# Frankie_DIYRevB.net
KiCad netlist of a schematic drawn in EAGLE
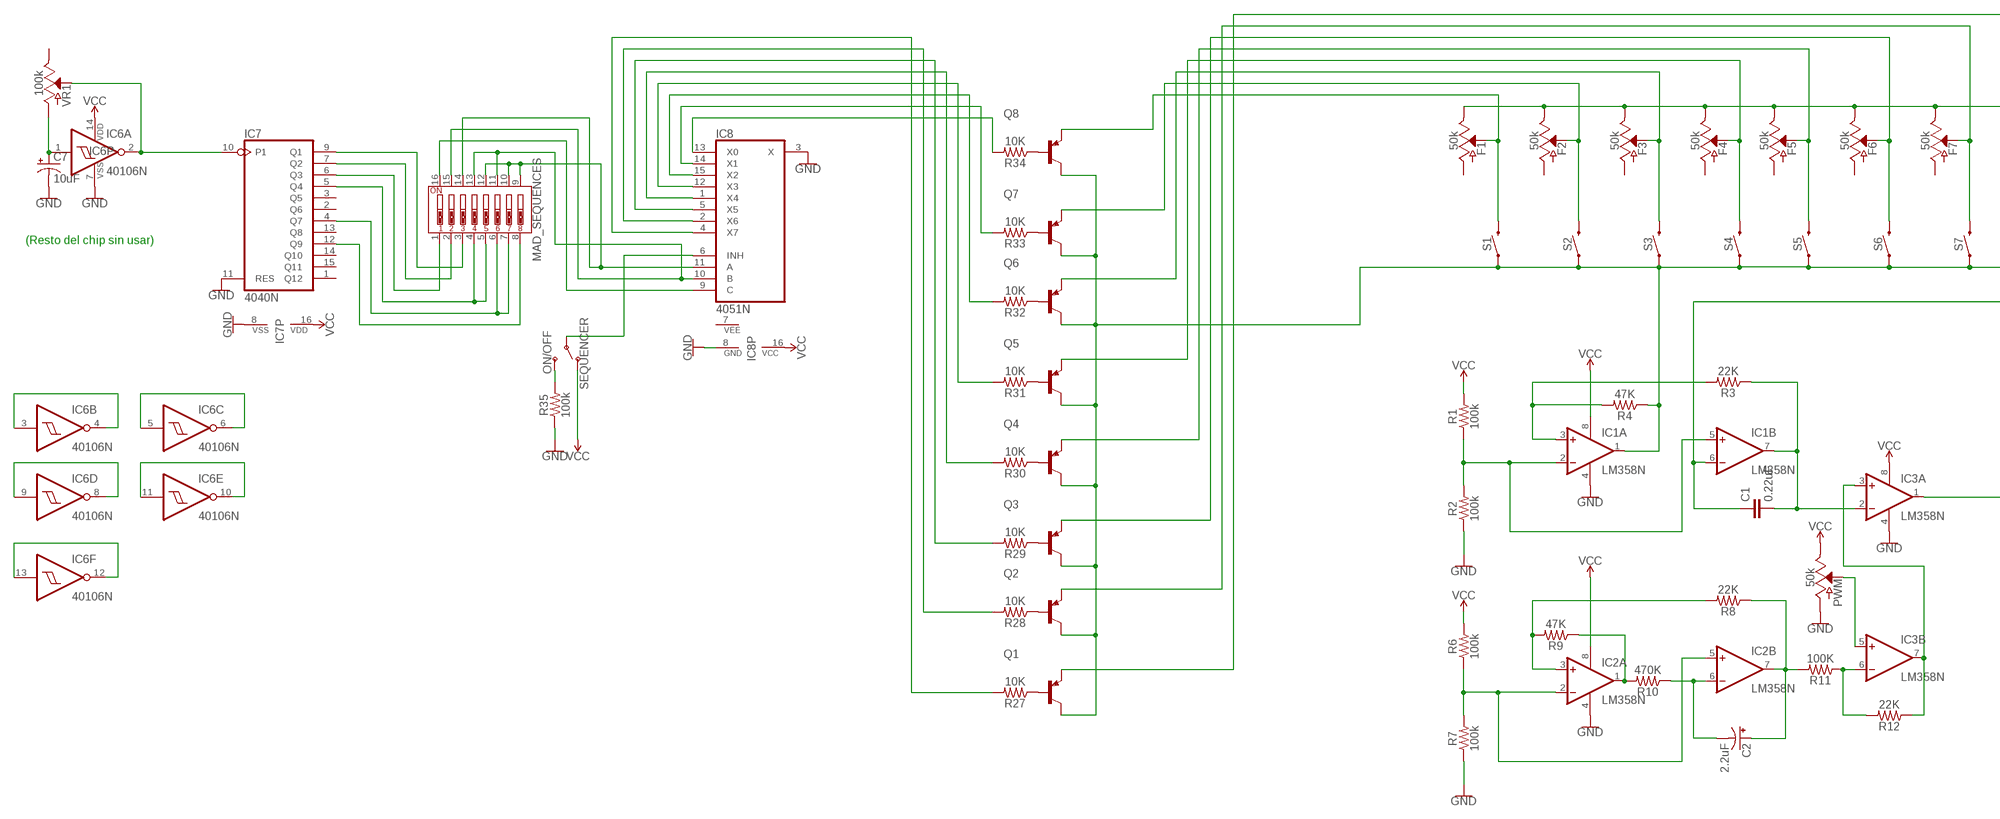
[diagram p0: schematic, sheet 1, part 1 of 2]
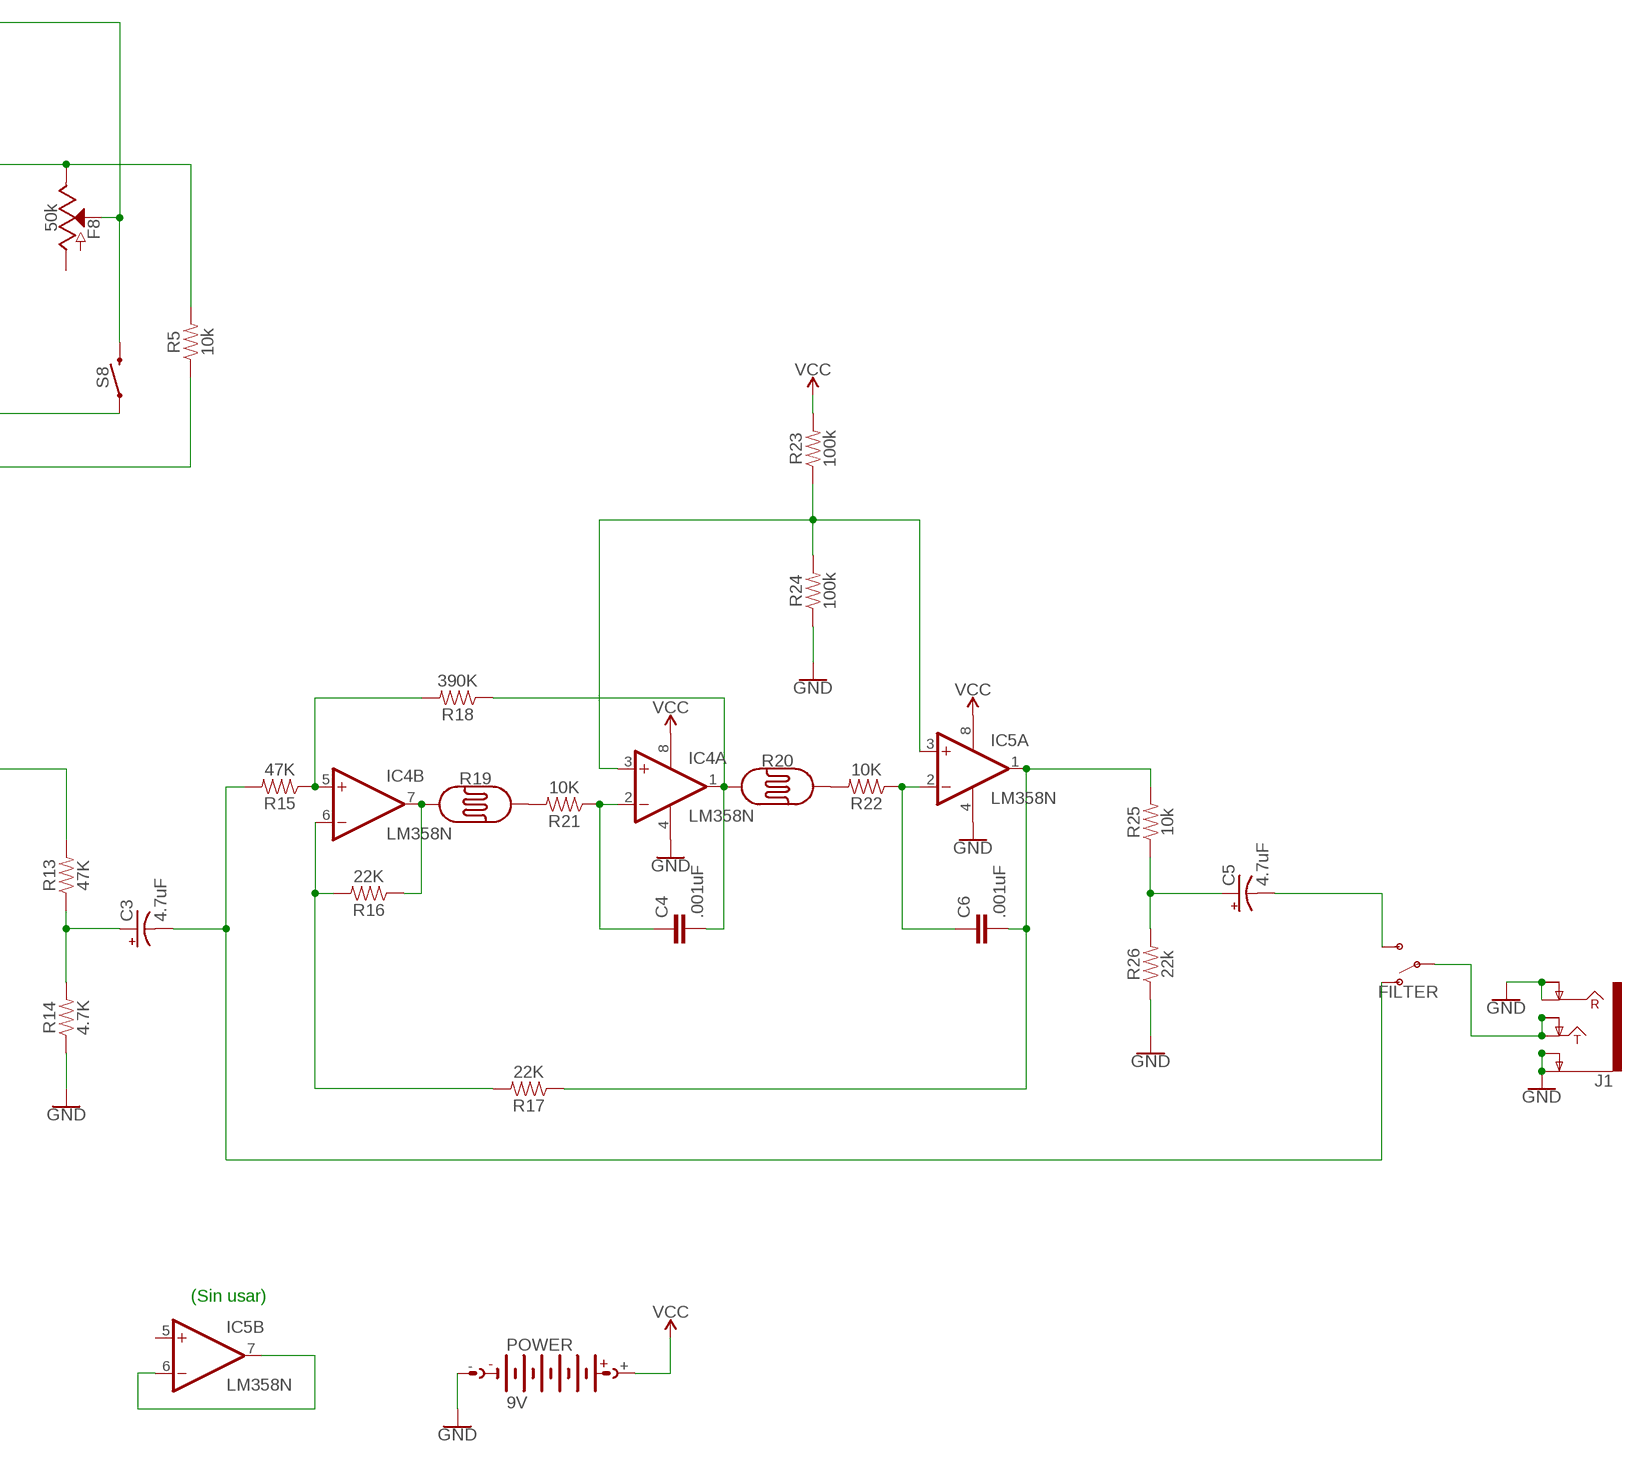
[diagram p1: schematic, sheet 1, part 2 of 2]

(export (version "E")
  (design (tool "Eeschema 10.0.6"))
  (components
    (comp (ref "C1")
      (value "0.22uF")
      (footprint "eagle-import:C5B2.5")
      (libsource (lib "eagle-import") (part "C5/2.5"))
    )
    (comp (ref "C2")
      (value "2.2uF")
      (footprint "eagle-import:CPOL-RADIAL-2.5MM-5MM-KIT")
      (libsource (lib "eagle-import") (part "10UF-POLAR-RADIAL-2.5MM-KIT-25V-20%"))
    )
    (comp (ref "C3")
      (value "4.7uF")
      (footprint "eagle-import:CPOL-RADIAL-2.5MM-5MM-KIT")
      (libsource (lib "eagle-import") (part "10UF-POLAR-RADIAL-2.5MM-KIT-25V-20%"))
    )
    (comp (ref "C4")
      (value ".001uF")
      (footprint "eagle-import:C5B2.5")
      (libsource (lib "eagle-import") (part "C5/2.5"))
    )
    (comp (ref "C5")
      (value "4.7uF")
      (footprint "eagle-import:CPOL-RADIAL-2.5MM-5MM-KIT")
      (libsource (lib "eagle-import") (part "10UF-POLAR-RADIAL-2.5MM-KIT-25V-20%"))
    )
    (comp (ref "C6")
      (value ".001uF")
      (footprint "eagle-import:C5B2.5")
      (libsource (lib "eagle-import") (part "C5/2.5"))
    )
    (comp (ref "C7")
      (value "10uF")
      (footprint "eagle-import:CPOL-RADIAL-2.5MM-5MM-KIT")
      (libsource (lib "eagle-import") (part "10UF-POLAR-RADIAL-2.5MM-KIT-25V-20%"))
    )
    (comp (ref "F1")
      (value "50k")
      (footprint "eagle-import:POT-PTH-ALPS-KIT")
      (libsource (lib "eagle-import") (part "POTENTIOMETER-PTH-9MM-1/20W-20%-KIT"))
    )
    (comp (ref "F2")
      (value "50k")
      (footprint "eagle-import:POT-PTH-ALPS-KIT")
      (libsource (lib "eagle-import") (part "POTENTIOMETER-PTH-9MM-1/20W-20%-KIT"))
    )
    (comp (ref "F3")
      (value "50k")
      (footprint "eagle-import:POT-PTH-ALPS-KIT")
      (libsource (lib "eagle-import") (part "POTENTIOMETER-PTH-9MM-1/20W-20%-KIT"))
    )
    (comp (ref "F4")
      (value "50k")
      (footprint "eagle-import:POT-PTH-ALPS-KIT")
      (libsource (lib "eagle-import") (part "POTENTIOMETER-PTH-9MM-1/20W-20%-KIT"))
    )
    (comp (ref "F5")
      (value "50k")
      (footprint "eagle-import:POT-PTH-ALPS-KIT")
      (libsource (lib "eagle-import") (part "POTENTIOMETER-PTH-9MM-1/20W-20%-KIT"))
    )
    (comp (ref "F6")
      (value "50k")
      (footprint "eagle-import:POT-PTH-ALPS-KIT")
      (libsource (lib "eagle-import") (part "POTENTIOMETER-PTH-9MM-1/20W-20%-KIT"))
    )
    (comp (ref "F7")
      (value "50k")
      (footprint "eagle-import:POT-PTH-ALPS-KIT")
      (libsource (lib "eagle-import") (part "POTENTIOMETER-PTH-9MM-1/20W-20%-KIT"))
    )
    (comp (ref "F8")
      (value "50k")
      (footprint "eagle-import:POT-PTH-ALPS-KIT")
      (libsource (lib "eagle-import") (part "POTENTIOMETER-PTH-9MM-1/20W-20%-KIT"))
    )
    (comp (ref "FILTER")
      (value "SWITCH-SPDT-PTH-11.6X4.0MM-KIT")
      (footprint "eagle-import:SWITCH_SPDT_PTH_11.6X4.0MM_KIT")
      (libsource (lib "eagle-import") (part "SWITCH-SPDT-PTH-11.6X4.0MM-KIT"))
    )
    (comp (ref "IC1")
      (value "LM358N")
      (footprint "eagle-import:DIL08")
      (libsource (lib "eagle-import") (part "LM358N"))
    )
    (comp (ref "IC2")
      (value "LM358N")
      (footprint "eagle-import:DIL08")
      (libsource (lib "eagle-import") (part "LM358N"))
    )
    (comp (ref "IC3")
      (value "LM358N")
      (footprint "eagle-import:DIL08")
      (libsource (lib "eagle-import") (part "LM358N"))
    )
    (comp (ref "IC4")
      (value "LM358N")
      (footprint "eagle-import:DIL08")
      (libsource (lib "eagle-import") (part "LM358N"))
    )
    (comp (ref "IC5")
      (value "LM358N")
      (footprint "eagle-import:DIL08")
      (libsource (lib "eagle-import") (part "LM358N"))
    )
    (comp (ref "IC6")
      (value "40106N")
      (footprint "eagle-import:DIL14")
      (libsource (lib "eagle-import") (part "40106N"))
    )
    (comp (ref "IC7")
      (value "4040N")
      (footprint "eagle-import:DIL16")
      (libsource (lib "eagle-import") (part "4040N"))
    )
    (comp (ref "IC8")
      (value "4051N")
      (footprint "eagle-import:DIL16")
      (libsource (lib "eagle-import") (part "4051N"))
    )
    (comp (ref "J1")
      (value "AUDIO_JACK_TRS_0.25\"_PTH_RA")
      (footprint "eagle-import:AUDIO_JACK_0.25__TRS_PTH_RA")
      (libsource (lib "eagle-import") (part "AUDIO_JACK_TRS_0.25{dblquote}_PTH_RA"))
    )
    (comp (ref "MAD_SEQUENCES")
      (value "DIP-08-PTH")
      (footprint "eagle-import:DIPSWITCH-08")
      (libsource (lib "eagle-import") (part "DIP-08-PTH"))
    )
    (comp (ref "POWER")
      (value "9V")
      (footprint "eagle-import:AB9V")
      (libsource (lib "eagle-import") (part "AB9V"))
    )
    (comp (ref "PWM")
      (value "50k")
      (footprint "eagle-import:POT-PTH-ALPS-KIT")
      (libsource (lib "eagle-import") (part "POTENTIOMETER-PTH-9MM-1/20W-20%-KIT"))
    )
    (comp (ref "Q1")
      (value "2N3906")
      (footprint "eagle-import:TO92")
      (libsource (lib "eagle-import") (part "2N3906"))
    )
    (comp (ref "Q2")
      (value "2N3906")
      (footprint "eagle-import:TO92")
      (libsource (lib "eagle-import") (part "2N3906"))
    )
    (comp (ref "Q3")
      (value "2N3906")
      (footprint "eagle-import:TO92")
      (libsource (lib "eagle-import") (part "2N3906"))
    )
    (comp (ref "Q4")
      (value "2N3906")
      (footprint "eagle-import:TO92")
      (libsource (lib "eagle-import") (part "2N3906"))
    )
    (comp (ref "Q5")
      (value "2N3906")
      (footprint "eagle-import:TO92")
      (libsource (lib "eagle-import") (part "2N3906"))
    )
    (comp (ref "Q6")
      (value "2N3906")
      (footprint "eagle-import:TO92")
      (libsource (lib "eagle-import") (part "2N3906"))
    )
    (comp (ref "Q7")
      (value "2N3906")
      (footprint "eagle-import:TO92")
      (libsource (lib "eagle-import") (part "2N3906"))
    )
    (comp (ref "Q8")
      (value "2N3906")
      (footprint "eagle-import:TO92")
      (libsource (lib "eagle-import") (part "2N3906"))
    )
    (comp (ref "R1")
      (value "100k")
      (footprint "eagle-import:AXIAL-0.3")
      (libsource (lib "eagle-import") (part "100KOHM-HORIZ-1/4W-5%"))
    )
    (comp (ref "R2")
      (value "100k")
      (footprint "eagle-import:AXIAL-0.3")
      (libsource (lib "eagle-import") (part "100KOHM-HORIZ-1/4W-5%"))
    )
    (comp (ref "R3")
      (value "22K")
      (footprint "eagle-import:AXIAL-0.3")
      (libsource (lib "eagle-import") (part "100KOHM-HORIZ-1/4W-5%"))
    )
    (comp (ref "R4")
      (value "47K")
      (footprint "eagle-import:AXIAL-0.3")
      (libsource (lib "eagle-import") (part "100KOHM-HORIZ-1/4W-5%"))
    )
    (comp (ref "R5")
      (value "10k")
      (footprint "eagle-import:AXIAL-0.3")
      (libsource (lib "eagle-import") (part "100KOHM-HORIZ-1/4W-5%"))
    )
    (comp (ref "R6")
      (value "100k")
      (footprint "eagle-import:AXIAL-0.3")
      (libsource (lib "eagle-import") (part "100KOHM-HORIZ-1/4W-5%"))
    )
    (comp (ref "R7")
      (value "100k")
      (footprint "eagle-import:AXIAL-0.3")
      (libsource (lib "eagle-import") (part "100KOHM-HORIZ-1/4W-5%"))
    )
    (comp (ref "R8")
      (value "22K")
      (footprint "eagle-import:AXIAL-0.3")
      (libsource (lib "eagle-import") (part "100KOHM-HORIZ-1/4W-5%"))
    )
    (comp (ref "R9")
      (value "47K")
      (footprint "eagle-import:AXIAL-0.3")
      (libsource (lib "eagle-import") (part "100KOHM-HORIZ-1/4W-5%"))
    )
    (comp (ref "R10")
      (value "470K")
      (footprint "eagle-import:AXIAL-0.3")
      (libsource (lib "eagle-import") (part "100KOHM-HORIZ-1/4W-5%"))
    )
    (comp (ref "R11")
      (value "100K")
      (footprint "eagle-import:AXIAL-0.3")
      (libsource (lib "eagle-import") (part "100KOHM-HORIZ-1/4W-5%"))
    )
    (comp (ref "R12")
      (value "22K")
      (footprint "eagle-import:AXIAL-0.3")
      (libsource (lib "eagle-import") (part "100KOHM-HORIZ-1/4W-5%"))
    )
    (comp (ref "R13")
      (value "47K")
      (footprint "eagle-import:AXIAL-0.3")
      (libsource (lib "eagle-import") (part "100KOHM-HORIZ-1/4W-5%"))
    )
    (comp (ref "R14")
      (value "4.7K")
      (footprint "eagle-import:AXIAL-0.3")
      (libsource (lib "eagle-import") (part "100KOHM-HORIZ-1/4W-5%"))
    )
    (comp (ref "R15")
      (value "47K")
      (footprint "eagle-import:AXIAL-0.3")
      (libsource (lib "eagle-import") (part "100KOHM-HORIZ-1/4W-5%"))
    )
    (comp (ref "R16")
      (value "22K")
      (footprint "eagle-import:AXIAL-0.3")
      (libsource (lib "eagle-import") (part "100KOHM-HORIZ-1/4W-5%"))
    )
    (comp (ref "R17")
      (value "22K")
      (footprint "eagle-import:AXIAL-0.3")
      (libsource (lib "eagle-import") (part "100KOHM-HORIZ-1/4W-5%"))
    )
    (comp (ref "R18")
      (value "390K")
      (footprint "eagle-import:AXIAL-0.3")
      (libsource (lib "eagle-import") (part "100KOHM-HORIZ-1/4W-5%"))
    )
    (comp (ref "R19")
      (value "PHOTOCELLPTH-KIT")
      (footprint "eagle-import:PHOTOCELL-KIT")
      (libsource (lib "eagle-import") (part "PHOTOCELLPTH-KIT"))
    )
    (comp (ref "R20")
      (value "PHOTOCELLPTH-KIT")
      (footprint "eagle-import:PHOTOCELL-KIT")
      (libsource (lib "eagle-import") (part "PHOTOCELLPTH-KIT"))
    )
    (comp (ref "R21")
      (value "10K")
      (footprint "eagle-import:AXIAL-0.3")
      (libsource (lib "eagle-import") (part "100KOHM-HORIZ-1/4W-5%"))
    )
    (comp (ref "R22")
      (value "10K")
      (footprint "eagle-import:AXIAL-0.3")
      (libsource (lib "eagle-import") (part "100KOHM-HORIZ-1/4W-5%"))
    )
    (comp (ref "R23")
      (value "100k")
      (footprint "eagle-import:AXIAL-0.3")
      (libsource (lib "eagle-import") (part "100KOHM-HORIZ-1/4W-5%"))
    )
    (comp (ref "R24")
      (value "100k")
      (footprint "eagle-import:AXIAL-0.3")
      (libsource (lib "eagle-import") (part "100KOHM-HORIZ-1/4W-5%"))
    )
    (comp (ref "R25")
      (value "10k")
      (footprint "eagle-import:AXIAL-0.3")
      (libsource (lib "eagle-import") (part "100KOHM-HORIZ-1/4W-5%"))
    )
    (comp (ref "R26")
      (value "22k")
      (footprint "eagle-import:AXIAL-0.3")
      (libsource (lib "eagle-import") (part "100KOHM-HORIZ-1/4W-5%"))
    )
    (comp (ref "R27")
      (value "10K")
      (footprint "eagle-import:AXIAL-0.3")
      (libsource (lib "eagle-import") (part "100KOHM-HORIZ-1/4W-5%"))
    )
    (comp (ref "R28")
      (value "10K")
      (footprint "eagle-import:AXIAL-0.3")
      (libsource (lib "eagle-import") (part "100KOHM-HORIZ-1/4W-5%"))
    )
    (comp (ref "R29")
      (value "10K")
      (footprint "eagle-import:AXIAL-0.3")
      (libsource (lib "eagle-import") (part "100KOHM-HORIZ-1/4W-5%"))
    )
    (comp (ref "R30")
      (value "10K")
      (footprint "eagle-import:AXIAL-0.3")
      (libsource (lib "eagle-import") (part "100KOHM-HORIZ-1/4W-5%"))
    )
    (comp (ref "R31")
      (value "10K")
      (footprint "eagle-import:AXIAL-0.3")
      (libsource (lib "eagle-import") (part "100KOHM-HORIZ-1/4W-5%"))
    )
    (comp (ref "R32")
      (value "10K")
      (footprint "eagle-import:AXIAL-0.3")
      (libsource (lib "eagle-import") (part "100KOHM-HORIZ-1/4W-5%"))
    )
    (comp (ref "R33")
      (value "10K")
      (footprint "eagle-import:AXIAL-0.3")
      (libsource (lib "eagle-import") (part "100KOHM-HORIZ-1/4W-5%"))
    )
    (comp (ref "R34")
      (value "10K")
      (footprint "eagle-import:AXIAL-0.3")
      (libsource (lib "eagle-import") (part "100KOHM-HORIZ-1/4W-5%"))
    )
    (comp (ref "R35")
      (value "100k")
      (footprint "eagle-import:AXIAL-0.3")
      (libsource (lib "eagle-import") (part "100KOHM-HORIZ-1/4W-5%"))
    )
    (comp (ref "S1")
      (value "MOMENTARY-SWITCH-SPST-PTH-12MM")
      (footprint "eagle-import:TACTILE_SWITCH_PTH_12MM")
      (libsource (lib "eagle-import") (part "MOMENTARY-SWITCH-SPST-PTH-12MM"))
    )
    (comp (ref "S2")
      (value "MOMENTARY-SWITCH-SPST-PTH-12MM")
      (footprint "eagle-import:TACTILE_SWITCH_PTH_12MM")
      (libsource (lib "eagle-import") (part "MOMENTARY-SWITCH-SPST-PTH-12MM"))
    )
    (comp (ref "S3")
      (value "MOMENTARY-SWITCH-SPST-PTH-12MM")
      (footprint "eagle-import:TACTILE_SWITCH_PTH_12MM")
      (libsource (lib "eagle-import") (part "MOMENTARY-SWITCH-SPST-PTH-12MM"))
    )
    (comp (ref "S4")
      (value "MOMENTARY-SWITCH-SPST-PTH-12MM")
      (footprint "eagle-import:TACTILE_SWITCH_PTH_12MM")
      (libsource (lib "eagle-import") (part "MOMENTARY-SWITCH-SPST-PTH-12MM"))
    )
    (comp (ref "S5")
      (value "MOMENTARY-SWITCH-SPST-PTH-12MM")
      (footprint "eagle-import:TACTILE_SWITCH_PTH_12MM")
      (libsource (lib "eagle-import") (part "MOMENTARY-SWITCH-SPST-PTH-12MM"))
    )
    (comp (ref "S6")
      (value "MOMENTARY-SWITCH-SPST-PTH-12MM")
      (footprint "eagle-import:TACTILE_SWITCH_PTH_12MM")
      (libsource (lib "eagle-import") (part "MOMENTARY-SWITCH-SPST-PTH-12MM"))
    )
    (comp (ref "S7")
      (value "MOMENTARY-SWITCH-SPST-PTH-12MM")
      (footprint "eagle-import:TACTILE_SWITCH_PTH_12MM")
      (libsource (lib "eagle-import") (part "MOMENTARY-SWITCH-SPST-PTH-12MM"))
    )
    (comp (ref "S8")
      (value "MOMENTARY-SWITCH-SPST-PTH-12MM")
      (footprint "eagle-import:TACTILE_SWITCH_PTH_12MM")
      (libsource (lib "eagle-import") (part "MOMENTARY-SWITCH-SPST-PTH-12MM"))
    )
    (comp (ref "SEQUENCER")
      (value "ON/OFF")
      (footprint "eagle-import:SWITCH_SPDT_PTH_11.6X4.0MM_KIT")
      (libsource (lib "eagle-import") (part "SWITCH-SPDT-PTH-11.6X4.0MM-KIT"))
    )
    (comp (ref "VR1")
      (value "100k")
      (footprint "eagle-import:POT-PTH-ALPS-KIT")
      (libsource (lib "eagle-import") (part "POTENTIOMETER-PTH-9MM-1/20W-20%-KIT"))
    )
  )
  (nets
    (net (code "1") (name "/VEE") (class "Default")
      (node (ref "IC8") (pin "7") (pinfunction "VEE_7") (pintype "power_in"))
    )
    (net (code "2") (name "GND") (class "Default")
      (node (ref "C7") (pin "2") (pinfunction "-_2") (pintype "passive"))
      (node (ref "IC1") (pin "4") (pinfunction "V-_4") (pintype "power_in"))
      (node (ref "IC2") (pin "4") (pinfunction "V-_4") (pintype "power_in"))
      (node (ref "IC3") (pin "4") (pinfunction "V-_4") (pintype "power_in"))
      (node (ref "IC4") (pin "4") (pinfunction "V-_4") (pintype "power_in"))
      (node (ref "IC5") (pin "4") (pinfunction "V-_4") (pintype "power_in"))
      (node (ref "IC6") (pin "7") (pinfunction "VSS_7") (pintype "power_in"))
      (node (ref "IC7") (pin "11") (pinfunction "RES_11") (pintype "input"))
      (node (ref "IC7") (pin "8") (pinfunction "VSS_8") (pintype "power_in"))
      (node (ref "IC8") (pin "3") (pinfunction "X_3") (pintype "bidirectional"))
      (node (ref "IC8") (pin "8") (pinfunction "GND_8") (pintype "power_in"))
      (node (ref "J1") (pin "RING") (pinfunction "RING_RING") (pintype "bidirectional"))
      (node (ref "J1") (pin "RING-NORM") (pinfunction "RING-NORM_RING-NORM") (pintype "bidirectional"))
      (node (ref "J1") (pin "SLEEVE") (pinfunction "EARTH_SLEEVE") (pintype "bidirectional"))
      (node (ref "J1") (pin "SLEEVE-NORM") (pinfunction "EARTH-NORM_SLEEVE-NORM") (pintype "bidirectional"))
      (node (ref "POWER") (pin "-") (pinfunction "-_-") (pintype "passive"))
      (node (ref "PWM") (pin "P$3") (pinfunction "A_P$3") (pintype "passive"))
      (node (ref "R14") (pin "P$1") (pinfunction "1_P$1") (pintype "passive"))
      (node (ref "R2") (pin "P$1") (pinfunction "1_P$1") (pintype "passive"))
      (node (ref "R24") (pin "P$1") (pinfunction "1_P$1") (pintype "passive"))
      (node (ref "R26") (pin "P$1") (pinfunction "1_P$1") (pintype "passive"))
      (node (ref "R35") (pin "P$1") (pinfunction "1_P$1") (pintype "passive"))
      (node (ref "R7") (pin "P$1") (pinfunction "1_P$1") (pintype "passive"))
    )
    (net (code "3") (name "Net-(C2-+)") (class "Default")
      (node (ref "C2") (pin "1") (pinfunction "+_1") (pintype "passive"))
      (node (ref "IC2") (pin "7") (pinfunction "OUT_7") (pintype "output"))
      (node (ref "R11") (pin "P$2") (pinfunction "2_P$2") (pintype "passive"))
      (node (ref "R8") (pin "P$1") (pinfunction "1_P$1") (pintype "passive"))
    )
    (net (code "4") (name "Net-(C2--)") (class "Default")
      (node (ref "C2") (pin "2") (pinfunction "-_2") (pintype "passive"))
      (node (ref "IC2") (pin "6") (pinfunction "-IN_6") (pintype "input"))
      (node (ref "R10") (pin "P$1") (pinfunction "1_P$1") (pintype "passive"))
    )
    (net (code "5") (name "Net-(C3-+)") (class "Default")
      (node (ref "C3") (pin "1") (pinfunction "+_1") (pintype "passive"))
      (node (ref "R13") (pin "P$1") (pinfunction "1_P$1") (pintype "passive"))
      (node (ref "R14") (pin "P$2") (pinfunction "2_P$2") (pintype "passive"))
    )
    (net (code "6") (name "Net-(C3--)") (class "Default")
      (node (ref "C3") (pin "2") (pinfunction "-_2") (pintype "passive"))
      (node (ref "FILTER") (pin "1") (pinfunction "O_1") (pintype "passive"))
      (node (ref "R15") (pin "P$2") (pinfunction "2_P$2") (pintype "passive"))
    )
    (net (code "7") (name "Net-(C5-+)") (class "Default")
      (node (ref "C5") (pin "1") (pinfunction "+_1") (pintype "passive"))
      (node (ref "R25") (pin "P$1") (pinfunction "1_P$1") (pintype "passive"))
      (node (ref "R26") (pin "P$2") (pinfunction "2_P$2") (pintype "passive"))
    )
    (net (code "8") (name "Net-(C5--)") (class "Default")
      (node (ref "C5") (pin "2") (pinfunction "-_2") (pintype "passive"))
      (node (ref "FILTER") (pin "3") (pinfunction "S_3") (pintype "passive"))
    )
    (net (code "9") (name "Net-(C7-+)") (class "Default")
      (node (ref "C7") (pin "1") (pinfunction "+_1") (pintype "passive"))
      (node (ref "IC6") (pin "1") (pinfunction "I_1") (pintype "input"))
      (node (ref "VR1") (pin "P$3") (pinfunction "A_P$3") (pintype "passive"))
    )
    (net (code "10") (name "Net-(F1-E)") (class "Default")
      (node (ref "F1") (pin "P$1") (pinfunction "E_P$1") (pintype "passive"))
      (node (ref "F2") (pin "P$1") (pinfunction "E_P$1") (pintype "passive"))
      (node (ref "F3") (pin "P$1") (pinfunction "E_P$1") (pintype "passive"))
      (node (ref "F4") (pin "P$1") (pinfunction "E_P$1") (pintype "passive"))
      (node (ref "F5") (pin "P$1") (pinfunction "E_P$1") (pintype "passive"))
      (node (ref "F6") (pin "P$1") (pinfunction "E_P$1") (pintype "passive"))
      (node (ref "F7") (pin "P$1") (pinfunction "E_P$1") (pintype "passive"))
      (node (ref "F8") (pin "P$1") (pinfunction "E_P$1") (pintype "passive"))
      (node (ref "R5") (pin "P$2") (pinfunction "2_P$2") (pintype "passive"))
    )
    (net (code "11") (name "Net-(F1-S)") (class "Default")
      (node (ref "F1") (pin "P$2") (pinfunction "S_P$2") (pintype "passive"))
      (node (ref "Q8") (pin "3") (pinfunction "E_3") (pintype "passive"))
      (node (ref "S1") (pin "3") (pinfunction "2_3") (pintype "passive"))
    )
    (net (code "12") (name "Net-(F2-S)") (class "Default")
      (node (ref "F2") (pin "P$2") (pinfunction "S_P$2") (pintype "passive"))
      (node (ref "Q7") (pin "3") (pinfunction "E_3") (pintype "passive"))
      (node (ref "S2") (pin "3") (pinfunction "2_3") (pintype "passive"))
    )
    (net (code "13") (name "Net-(F3-S)") (class "Default")
      (node (ref "F3") (pin "P$2") (pinfunction "S_P$2") (pintype "passive"))
      (node (ref "Q6") (pin "3") (pinfunction "E_3") (pintype "passive"))
      (node (ref "S3") (pin "3") (pinfunction "2_3") (pintype "passive"))
    )
    (net (code "14") (name "Net-(F4-S)") (class "Default")
      (node (ref "F4") (pin "P$2") (pinfunction "S_P$2") (pintype "passive"))
      (node (ref "Q5") (pin "3") (pinfunction "E_3") (pintype "passive"))
      (node (ref "S4") (pin "3") (pinfunction "2_3") (pintype "passive"))
    )
    (net (code "15") (name "Net-(F5-S)") (class "Default")
      (node (ref "F5") (pin "P$2") (pinfunction "S_P$2") (pintype "passive"))
      (node (ref "Q4") (pin "3") (pinfunction "E_3") (pintype "passive"))
      (node (ref "S5") (pin "3") (pinfunction "2_3") (pintype "passive"))
    )
    (net (code "16") (name "Net-(F6-S)") (class "Default")
      (node (ref "F6") (pin "P$2") (pinfunction "S_P$2") (pintype "passive"))
      (node (ref "Q3") (pin "3") (pinfunction "E_3") (pintype "passive"))
      (node (ref "S6") (pin "3") (pinfunction "2_3") (pintype "passive"))
    )
    (net (code "17") (name "Net-(F7-S)") (class "Default")
      (node (ref "F7") (pin "P$2") (pinfunction "S_P$2") (pintype "passive"))
      (node (ref "Q2") (pin "3") (pinfunction "E_3") (pintype "passive"))
      (node (ref "S7") (pin "3") (pinfunction "2_3") (pintype "passive"))
    )
    (net (code "18") (name "Net-(F8-S)") (class "Default")
      (node (ref "F8") (pin "P$2") (pinfunction "S_P$2") (pintype "passive"))
      (node (ref "Q1") (pin "3") (pinfunction "E_3") (pintype "passive"))
      (node (ref "S8") (pin "3") (pinfunction "2_3") (pintype "passive"))
    )
    (net (code "19") (name "Net-(FILTER-P)") (class "Default")
      (node (ref "FILTER") (pin "2") (pinfunction "P_2") (pintype "passive"))
      (node (ref "J1") (pin "TIP") (pinfunction "TIP_TIP") (pintype "bidirectional"))
      (node (ref "J1") (pin "TIP-NORM") (pinfunction "TIP-NORM_TIP-NORM") (pintype "bidirectional"))
    )
    (net (code "20") (name "Net-(IC1A-+IN)") (class "Default")
      (node (ref "IC1") (pin "3") (pinfunction "+IN_3") (pintype "input"))
      (node (ref "R3") (pin "P$2") (pinfunction "2_P$2") (pintype "passive"))
      (node (ref "R4") (pin "P$2") (pinfunction "2_P$2") (pintype "passive"))
    )
    (net (code "21") (name "Net-(IC1A--IN)") (class "Default")
      (node (ref "IC1") (pin "2") (pinfunction "-IN_2") (pintype "input"))
      (node (ref "IC1") (pin "5") (pinfunction "+IN_5") (pintype "input"))
      (node (ref "R1") (pin "P$1") (pinfunction "1_P$1") (pintype "passive"))
      (node (ref "R2") (pin "P$2") (pinfunction "2_P$2") (pintype "passive"))
    )
    (net (code "22") (name "Net-(IC1A-OUT)") (class "Default")
      (node (ref "IC1") (pin "1") (pinfunction "OUT_1") (pintype "output"))
      (node (ref "Q1") (pin "1") (pinfunction "C_1") (pintype "passive"))
      (node (ref "Q2") (pin "1") (pinfunction "C_1") (pintype "passive"))
      (node (ref "Q3") (pin "1") (pinfunction "C_1") (pintype "passive"))
      (node (ref "Q4") (pin "1") (pinfunction "C_1") (pintype "passive"))
      (node (ref "Q5") (pin "1") (pinfunction "C_1") (pintype "passive"))
      (node (ref "Q6") (pin "1") (pinfunction "C_1") (pintype "passive"))
      (node (ref "Q7") (pin "1") (pinfunction "C_1") (pintype "passive"))
      (node (ref "Q8") (pin "1") (pinfunction "C_1") (pintype "passive"))
      (node (ref "R4") (pin "P$1") (pinfunction "1_P$1") (pintype "passive"))
      (node (ref "S1") (pin "1") (pinfunction "1_1") (pintype "passive"))
      (node (ref "S2") (pin "1") (pinfunction "1_1") (pintype "passive"))
      (node (ref "S3") (pin "1") (pinfunction "1_1") (pintype "passive"))
      (node (ref "S4") (pin "1") (pinfunction "1_1") (pintype "passive"))
      (node (ref "S5") (pin "1") (pinfunction "1_1") (pintype "passive"))
      (node (ref "S6") (pin "1") (pinfunction "1_1") (pintype "passive"))
      (node (ref "S7") (pin "1") (pinfunction "1_1") (pintype "passive"))
      (node (ref "S8") (pin "1") (pinfunction "1_1") (pintype "passive"))
    )
    (net (code "23") (name "Net-(IC1B--IN)") (class "Default")
      (node (ref "C1") (pin "1") (pinfunction "1_1") (pintype "passive"))
      (node (ref "IC1") (pin "6") (pinfunction "-IN_6") (pintype "input"))
      (node (ref "R5") (pin "P$1") (pinfunction "1_P$1") (pintype "passive"))
    )
    (net (code "24") (name "Net-(IC1B-OUT)") (class "Default")
      (node (ref "C1") (pin "2") (pinfunction "2_2") (pintype "passive"))
      (node (ref "IC1") (pin "7") (pinfunction "OUT_7") (pintype "output"))
      (node (ref "IC3") (pin "2") (pinfunction "-IN_2") (pintype "input"))
      (node (ref "R3") (pin "P$1") (pinfunction "1_P$1") (pintype "passive"))
    )
    (net (code "25") (name "Net-(IC2A-+IN)") (class "Default")
      (node (ref "IC2") (pin "3") (pinfunction "+IN_3") (pintype "input"))
      (node (ref "R8") (pin "P$2") (pinfunction "2_P$2") (pintype "passive"))
      (node (ref "R9") (pin "P$2") (pinfunction "2_P$2") (pintype "passive"))
    )
    (net (code "26") (name "Net-(IC2A--IN)") (class "Default")
      (node (ref "IC2") (pin "2") (pinfunction "-IN_2") (pintype "input"))
      (node (ref "IC2") (pin "5") (pinfunction "+IN_5") (pintype "input"))
      (node (ref "R6") (pin "P$1") (pinfunction "1_P$1") (pintype "passive"))
      (node (ref "R7") (pin "P$2") (pinfunction "2_P$2") (pintype "passive"))
    )
    (net (code "27") (name "Net-(IC2A-OUT)") (class "Default")
      (node (ref "IC2") (pin "1") (pinfunction "OUT_1") (pintype "output"))
      (node (ref "R10") (pin "P$2") (pinfunction "2_P$2") (pintype "passive"))
      (node (ref "R9") (pin "P$1") (pinfunction "1_P$1") (pintype "passive"))
    )
    (net (code "28") (name "Net-(IC3A-+IN)") (class "Default")
      (node (ref "IC3") (pin "3") (pinfunction "+IN_3") (pintype "input"))
      (node (ref "IC3") (pin "7") (pinfunction "OUT_7") (pintype "output"))
      (node (ref "R12") (pin "P$1") (pinfunction "1_P$1") (pintype "passive"))
    )
    (net (code "29") (name "Net-(IC3A-OUT)") (class "Default")
      (node (ref "IC3") (pin "1") (pinfunction "OUT_1") (pintype "output"))
      (node (ref "R13") (pin "P$2") (pinfunction "2_P$2") (pintype "passive"))
    )
    (net (code "30") (name "Net-(IC3B-+IN)") (class "Default")
      (node (ref "IC3") (pin "5") (pinfunction "+IN_5") (pintype "input"))
      (node (ref "PWM") (pin "P$2") (pinfunction "S_P$2") (pintype "passive"))
    )
    (net (code "31") (name "Net-(IC3B--IN)") (class "Default")
      (node (ref "IC3") (pin "6") (pinfunction "-IN_6") (pintype "input"))
      (node (ref "R11") (pin "P$1") (pinfunction "1_P$1") (pintype "passive"))
      (node (ref "R12") (pin "P$2") (pinfunction "2_P$2") (pintype "passive"))
    )
    (net (code "32") (name "Net-(IC4A-+IN)") (class "Default")
      (node (ref "IC4") (pin "3") (pinfunction "+IN_3") (pintype "input"))
      (node (ref "IC5") (pin "3") (pinfunction "+IN_3") (pintype "input"))
      (node (ref "R23") (pin "P$1") (pinfunction "1_P$1") (pintype "passive"))
      (node (ref "R24") (pin "P$2") (pinfunction "2_P$2") (pintype "passive"))
    )
    (net (code "33") (name "Net-(IC4A--IN)") (class "Default")
      (node (ref "C4") (pin "1") (pinfunction "1_1") (pintype "passive"))
      (node (ref "IC4") (pin "2") (pinfunction "-IN_2") (pintype "input"))
      (node (ref "R21") (pin "P$1") (pinfunction "1_P$1") (pintype "passive"))
    )
    (net (code "34") (name "Net-(IC4A-OUT)") (class "Default")
      (node (ref "C4") (pin "2") (pinfunction "2_2") (pintype "passive"))
      (node (ref "IC4") (pin "1") (pinfunction "OUT_1") (pintype "output"))
      (node (ref "R18") (pin "P$1") (pinfunction "1_P$1") (pintype "passive"))
      (node (ref "R20") (pin "1") (pinfunction "P$1_1") (pintype "bidirectional"))
    )
    (net (code "35") (name "Net-(IC4B-+IN)") (class "Default")
      (node (ref "IC4") (pin "5") (pinfunction "+IN_5") (pintype "input"))
      (node (ref "R15") (pin "P$1") (pinfunction "1_P$1") (pintype "passive"))
      (node (ref "R18") (pin "P$2") (pinfunction "2_P$2") (pintype "passive"))
    )
    (net (code "36") (name "Net-(IC4B--IN)") (class "Default")
      (node (ref "IC4") (pin "6") (pinfunction "-IN_6") (pintype "input"))
      (node (ref "R16") (pin "P$2") (pinfunction "2_P$2") (pintype "passive"))
      (node (ref "R17") (pin "P$2") (pinfunction "2_P$2") (pintype "passive"))
    )
    (net (code "37") (name "Net-(IC4B-OUT)") (class "Default")
      (node (ref "IC4") (pin "7") (pinfunction "OUT_7") (pintype "output"))
      (node (ref "R16") (pin "P$1") (pinfunction "1_P$1") (pintype "passive"))
      (node (ref "R19") (pin "1") (pinfunction "P$1_1") (pintype "bidirectional"))
    )
    (net (code "38") (name "Net-(IC5A--IN)") (class "Default")
      (node (ref "C6") (pin "1") (pinfunction "1_1") (pintype "passive"))
      (node (ref "IC5") (pin "2") (pinfunction "-IN_2") (pintype "input"))
      (node (ref "R22") (pin "P$1") (pinfunction "1_P$1") (pintype "passive"))
    )
    (net (code "39") (name "Net-(IC5A-OUT)") (class "Default")
      (node (ref "C6") (pin "2") (pinfunction "2_2") (pintype "passive"))
      (node (ref "IC5") (pin "1") (pinfunction "OUT_1") (pintype "output"))
      (node (ref "R17") (pin "P$1") (pinfunction "1_P$1") (pintype "passive"))
      (node (ref "R25") (pin "P$2") (pinfunction "2_P$2") (pintype "passive"))
    )
    (net (code "40") (name "Net-(IC5B--IN)") (class "Default")
      (node (ref "IC5") (pin "6") (pinfunction "-IN_6") (pintype "input"))
      (node (ref "IC5") (pin "7") (pinfunction "OUT_7") (pintype "output"))
    )
    (net (code "41") (name "Net-(IC6A-O)") (class "Default")
      (node (ref "IC6") (pin "2") (pinfunction "O_2") (pintype "output"))
      (node (ref "IC7") (pin "10") (pinfunction "P1_10") (pintype "input"))
      (node (ref "VR1") (pin "P$2") (pinfunction "S_P$2") (pintype "passive"))
    )
    (net (code "42") (name "Net-(IC6B-I)") (class "Default")
      (node (ref "IC6") (pin "3") (pinfunction "I_3") (pintype "input"))
      (node (ref "IC6") (pin "4") (pinfunction "O_4") (pintype "output"))
    )
    (net (code "43") (name "Net-(IC6C-I)") (class "Default")
      (node (ref "IC6") (pin "5") (pinfunction "I_5") (pintype "input"))
      (node (ref "IC6") (pin "6") (pinfunction "O_6") (pintype "output"))
    )
    (net (code "44") (name "Net-(IC6D-I)") (class "Default")
      (node (ref "IC6") (pin "8") (pinfunction "O_8") (pintype "output"))
      (node (ref "IC6") (pin "9") (pinfunction "I_9") (pintype "input"))
    )
    (net (code "45") (name "Net-(IC6E-I)") (class "Default")
      (node (ref "IC6") (pin "10") (pinfunction "O_10") (pintype "output"))
      (node (ref "IC6") (pin "11") (pinfunction "I_11") (pintype "input"))
    )
    (net (code "46") (name "Net-(IC6F-I)") (class "Default")
      (node (ref "IC6") (pin "12") (pinfunction "O_12") (pintype "output"))
      (node (ref "IC6") (pin "13") (pinfunction "I_13") (pintype "input"))
    )
    (net (code "47") (name "Net-(IC7A-Q1)") (class "Default")
      (node (ref "IC7") (pin "9") (pinfunction "Q1_9") (pintype "output"))
      (node (ref "MAD_SEQUENCES") (pin "3") (pinfunction "3_3") (pintype "passive"))
    )
    (net (code "48") (name "Net-(IC7A-Q2)") (class "Default")
      (node (ref "IC7") (pin "7") (pinfunction "Q2_7") (pintype "output"))
      (node (ref "MAD_SEQUENCES") (pin "2") (pinfunction "2_2") (pintype "passive"))
    )
    (net (code "49") (name "Net-(IC7A-Q3)") (class "Default")
      (node (ref "IC7") (pin "6") (pinfunction "Q3_6") (pintype "output"))
      (node (ref "MAD_SEQUENCES") (pin "1") (pinfunction "1_1") (pintype "passive"))
    )
    (net (code "50") (name "Net-(IC7A-Q4)") (class "Default")
      (node (ref "IC7") (pin "5") (pinfunction "Q4_5") (pintype "output"))
      (node (ref "MAD_SEQUENCES") (pin "4") (pinfunction "4_4") (pintype "passive"))
      (node (ref "MAD_SEQUENCES") (pin "5") (pinfunction "5_5") (pintype "passive"))
    )
    (net (code "51") (name "Net-(IC7A-Q7)") (class "Default")
      (node (ref "IC7") (pin "4") (pinfunction "Q7_4") (pintype "output"))
      (node (ref "MAD_SEQUENCES") (pin "6") (pinfunction "6_6") (pintype "passive"))
      (node (ref "MAD_SEQUENCES") (pin "7") (pinfunction "7_7") (pintype "passive"))
    )
    (net (code "52") (name "Net-(IC7A-Q9)") (class "Default")
      (node (ref "IC7") (pin "12") (pinfunction "Q9_12") (pintype "output"))
      (node (ref "MAD_SEQUENCES") (pin "8") (pinfunction "8_8") (pintype "passive"))
    )
    (net (code "53") (name "Net-(IC8A-A)") (class "Default")
      (node (ref "IC8") (pin "11") (pinfunction "A_11") (pintype "input"))
      (node (ref "MAD_SEQUENCES") (pin "10") (pinfunction "10_10") (pintype "passive"))
      (node (ref "MAD_SEQUENCES") (pin "12") (pinfunction "12_12") (pintype "passive"))
      (node (ref "MAD_SEQUENCES") (pin "14") (pinfunction "14_14") (pintype "passive"))
      (node (ref "MAD_SEQUENCES") (pin "9") (pinfunction "9_9") (pintype "passive"))
    )
    (net (code "54") (name "Net-(IC8A-B)") (class "Default")
      (node (ref "IC8") (pin "10") (pinfunction "B_10") (pintype "input"))
      (node (ref "MAD_SEQUENCES") (pin "11") (pinfunction "11_11") (pintype "passive"))
      (node (ref "MAD_SEQUENCES") (pin "13") (pinfunction "13_13") (pintype "passive"))
      (node (ref "MAD_SEQUENCES") (pin "15") (pinfunction "15_15") (pintype "passive"))
    )
    (net (code "55") (name "Net-(IC8A-C)") (class "Default")
      (node (ref "IC8") (pin "9") (pinfunction "C_9") (pintype "input"))
      (node (ref "MAD_SEQUENCES") (pin "16") (pinfunction "16_16") (pintype "passive"))
    )
    (net (code "56") (name "Net-(IC8A-INH)") (class "Default")
      (node (ref "IC8") (pin "6") (pinfunction "INH_6") (pintype "input"))
      (node (ref "SEQUENCER") (pin "2") (pinfunction "P_2") (pintype "passive"))
    )
    (net (code "57") (name "Net-(IC8A-X0)") (class "Default")
      (node (ref "IC8") (pin "13") (pinfunction "X0_13") (pintype "bidirectional"))
      (node (ref "R34") (pin "P$2") (pinfunction "2_P$2") (pintype "passive"))
    )
    (net (code "58") (name "Net-(IC8A-X1)") (class "Default")
      (node (ref "IC8") (pin "14") (pinfunction "X1_14") (pintype "bidirectional"))
      (node (ref "R33") (pin "P$2") (pinfunction "2_P$2") (pintype "passive"))
    )
    (net (code "59") (name "Net-(IC8A-X2)") (class "Default")
      (node (ref "IC8") (pin "15") (pinfunction "X2_15") (pintype "bidirectional"))
      (node (ref "R32") (pin "P$2") (pinfunction "2_P$2") (pintype "passive"))
    )
    (net (code "60") (name "Net-(IC8A-X3)") (class "Default")
      (node (ref "IC8") (pin "12") (pinfunction "X3_12") (pintype "bidirectional"))
      (node (ref "R31") (pin "P$2") (pinfunction "2_P$2") (pintype "passive"))
    )
    (net (code "61") (name "Net-(IC8A-X4)") (class "Default")
      (node (ref "IC8") (pin "1") (pinfunction "X4_1") (pintype "bidirectional"))
      (node (ref "R30") (pin "P$2") (pinfunction "2_P$2") (pintype "passive"))
    )
    (net (code "62") (name "Net-(IC8A-X5)") (class "Default")
      (node (ref "IC8") (pin "5") (pinfunction "X5_5") (pintype "bidirectional"))
      (node (ref "R29") (pin "P$2") (pinfunction "2_P$2") (pintype "passive"))
    )
    (net (code "63") (name "Net-(IC8A-X6)") (class "Default")
      (node (ref "IC8") (pin "2") (pinfunction "X6_2") (pintype "bidirectional"))
      (node (ref "R28") (pin "P$2") (pinfunction "2_P$2") (pintype "passive"))
    )
    (net (code "64") (name "Net-(IC8A-X7)") (class "Default")
      (node (ref "IC8") (pin "4") (pinfunction "X7_4") (pintype "bidirectional"))
      (node (ref "R27") (pin "P$2") (pinfunction "2_P$2") (pintype "passive"))
    )
    (net (code "65") (name "Net-(Q1-B)") (class "Default")
      (node (ref "Q1") (pin "2") (pinfunction "B_2") (pintype "passive"))
      (node (ref "R27") (pin "P$1") (pinfunction "1_P$1") (pintype "passive"))
    )
    (net (code "66") (name "Net-(Q2-B)") (class "Default")
      (node (ref "Q2") (pin "2") (pinfunction "B_2") (pintype "passive"))
      (node (ref "R28") (pin "P$1") (pinfunction "1_P$1") (pintype "passive"))
    )
    (net (code "67") (name "Net-(Q3-B)") (class "Default")
      (node (ref "Q3") (pin "2") (pinfunction "B_2") (pintype "passive"))
      (node (ref "R29") (pin "P$1") (pinfunction "1_P$1") (pintype "passive"))
    )
    (net (code "68") (name "Net-(Q4-B)") (class "Default")
      (node (ref "Q4") (pin "2") (pinfunction "B_2") (pintype "passive"))
      (node (ref "R30") (pin "P$1") (pinfunction "1_P$1") (pintype "passive"))
    )
    (net (code "69") (name "Net-(Q5-B)") (class "Default")
      (node (ref "Q5") (pin "2") (pinfunction "B_2") (pintype "passive"))
      (node (ref "R31") (pin "P$1") (pinfunction "1_P$1") (pintype "passive"))
    )
    (net (code "70") (name "Net-(Q6-B)") (class "Default")
      (node (ref "Q6") (pin "2") (pinfunction "B_2") (pintype "passive"))
      (node (ref "R32") (pin "P$1") (pinfunction "1_P$1") (pintype "passive"))
    )
    (net (code "71") (name "Net-(Q7-B)") (class "Default")
      (node (ref "Q7") (pin "2") (pinfunction "B_2") (pintype "passive"))
      (node (ref "R33") (pin "P$1") (pinfunction "1_P$1") (pintype "passive"))
    )
    (net (code "72") (name "Net-(Q8-B)") (class "Default")
      (node (ref "Q8") (pin "2") (pinfunction "B_2") (pintype "passive"))
      (node (ref "R34") (pin "P$1") (pinfunction "1_P$1") (pintype "passive"))
    )
    (net (code "73") (name "Net-(R19-P$2)") (class "Default")
      (node (ref "R19") (pin "2") (pinfunction "P$2_2") (pintype "bidirectional"))
      (node (ref "R21") (pin "P$2") (pinfunction "2_P$2") (pintype "passive"))
    )
    (net (code "74") (name "Net-(R20-P$2)") (class "Default")
      (node (ref "R20") (pin "2") (pinfunction "P$2_2") (pintype "bidirectional"))
      (node (ref "R22") (pin "P$2") (pinfunction "2_P$2") (pintype "passive"))
    )
    (net (code "75") (name "Net-(R35-2)") (class "Default")
      (node (ref "R35") (pin "P$2") (pinfunction "2_P$2") (pintype "passive"))
      (node (ref "SEQUENCER") (pin "3") (pinfunction "S_3") (pintype "passive"))
    )
    (net (code "76") (name "VCC") (class "Default")
      (node (ref "IC1") (pin "8") (pinfunction "V+_8") (pintype "power_in"))
      (node (ref "IC2") (pin "8") (pinfunction "V+_8") (pintype "power_in"))
      (node (ref "IC3") (pin "8") (pinfunction "V+_8") (pintype "power_in"))
      (node (ref "IC4") (pin "8") (pinfunction "V+_8") (pintype "power_in"))
      (node (ref "IC5") (pin "8") (pinfunction "V+_8") (pintype "power_in"))
      (node (ref "IC6") (pin "14") (pinfunction "VDD_14") (pintype "power_in"))
      (node (ref "IC7") (pin "16") (pinfunction "VDD_16") (pintype "power_in"))
      (node (ref "IC8") (pin "16") (pinfunction "VCC_16") (pintype "power_in"))
      (node (ref "POWER") (pin "+") (pinfunction "+_+") (pintype "passive"))
      (node (ref "PWM") (pin "P$1") (pinfunction "E_P$1") (pintype "passive"))
      (node (ref "R1") (pin "P$2") (pinfunction "2_P$2") (pintype "passive"))
      (node (ref "R23") (pin "P$2") (pinfunction "2_P$2") (pintype "passive"))
      (node (ref "R6") (pin "P$2") (pinfunction "2_P$2") (pintype "passive"))
      (node (ref "SEQUENCER") (pin "1") (pinfunction "O_1") (pintype "passive"))
    )
    (net (code "77") (name "unconnected-(F1-A-PadP$3)") (class "Default")
      (node (ref "F1") (pin "P$3") (pinfunction "A_P$3") (pintype "passive"))
    )
    (net (code "78") (name "unconnected-(F2-A-PadP$3)") (class "Default")
      (node (ref "F2") (pin "P$3") (pinfunction "A_P$3") (pintype "passive"))
    )
    (net (code "79") (name "unconnected-(F3-A-PadP$3)") (class "Default")
      (node (ref "F3") (pin "P$3") (pinfunction "A_P$3") (pintype "passive"))
    )
    (net (code "80") (name "unconnected-(F4-A-PadP$3)") (class "Default")
      (node (ref "F4") (pin "P$3") (pinfunction "A_P$3") (pintype "passive"))
    )
    (net (code "81") (name "unconnected-(F5-A-PadP$3)") (class "Default")
      (node (ref "F5") (pin "P$3") (pinfunction "A_P$3") (pintype "passive"))
    )
    (net (code "82") (name "unconnected-(F6-A-PadP$3)") (class "Default")
      (node (ref "F6") (pin "P$3") (pinfunction "A_P$3") (pintype "passive"))
    )
    (net (code "83") (name "unconnected-(F7-A-PadP$3)") (class "Default")
      (node (ref "F7") (pin "P$3") (pinfunction "A_P$3") (pintype "passive"))
    )
    (net (code "84") (name "unconnected-(F8-A-PadP$3)") (class "Default")
      (node (ref "F8") (pin "P$3") (pinfunction "A_P$3") (pintype "passive"))
    )
    (net (code "85") (name "unconnected-(IC5B-+IN-Pad5)") (class "Default")
      (node (ref "IC5") (pin "5") (pinfunction "+IN_5") (pintype "input"))
    )
    (net (code "86") (name "unconnected-(IC7A-Q5-Pad3)") (class "Default")
      (node (ref "IC7") (pin "3") (pinfunction "Q5_3") (pintype "output"))
    )
    (net (code "87") (name "unconnected-(IC7A-Q6-Pad2)") (class "Default")
      (node (ref "IC7") (pin "2") (pinfunction "Q6_2") (pintype "output"))
    )
    (net (code "88") (name "unconnected-(IC7A-Q8-Pad13)") (class "Default")
      (node (ref "IC7") (pin "13") (pinfunction "Q8_13") (pintype "output"))
    )
    (net (code "89") (name "unconnected-(IC7A-Q10-Pad14)") (class "Default")
      (node (ref "IC7") (pin "14") (pinfunction "Q10_14") (pintype "output"))
    )
    (net (code "90") (name "unconnected-(IC7A-Q11-Pad15)") (class "Default")
      (node (ref "IC7") (pin "15") (pinfunction "Q11_15") (pintype "output"))
    )
    (net (code "91") (name "unconnected-(IC7A-Q12-Pad1)") (class "Default")
      (node (ref "IC7") (pin "1") (pinfunction "Q12_1") (pintype "output"))
    )
    (net (code "92") (name "unconnected-(VR1-E-PadP$1)") (class "Default")
      (node (ref "VR1") (pin "P$1") (pinfunction "E_P$1") (pintype "passive"))
    )
  )
)
